# ActiveHeadphone.net
KiCad netlist of a schematic drawn in EAGLE
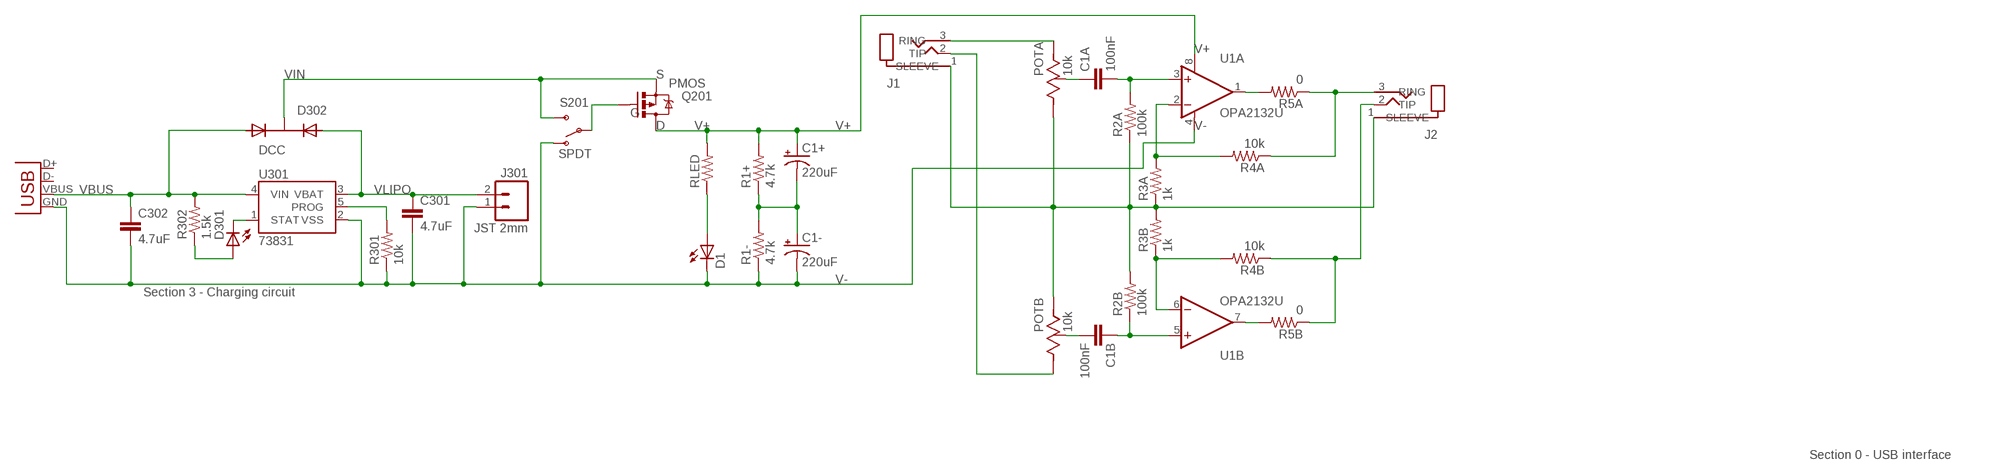
[diagram p0: schematic, sheet 1]

(export (version "E")
  (design (tool "Eeschema 10.0.6"))
  (components
    (comp (ref "C1+")
      (value "220uF")
      (footprint "eagle-import:EIA7343")
      (libsource (lib "eagle-import") (part "CAP_POL7343"))
    )
    (comp (ref "C1-")
      (value "220uF")
      (footprint "eagle-import:EIA7343")
      (libsource (lib "eagle-import") (part "CAP_POL7343"))
    )
    (comp (ref "C1A")
      (value "100nF")
      (footprint "eagle-import:0603-CAP")
      (libsource (lib "eagle-import") (part "CAP0603-CAP"))
    )
    (comp (ref "C1B")
      (value "100nF")
      (footprint "eagle-import:0603-CAP")
      (libsource (lib "eagle-import") (part "CAP0603-CAP"))
    )
    (comp (ref "C301")
      (value "4.7uF")
      (footprint "eagle-import:0603-CAP")
      (libsource (lib "eagle-import") (part "CAP0603-CAP"))
    )
    (comp (ref "C302")
      (value "4.7uF")
      (footprint "eagle-import:0603-CAP")
      (libsource (lib "eagle-import") (part "CAP0603-CAP"))
    )
    (comp (ref "D1")
      (value "RED")
      (footprint "eagle-import:LED-0603")
      (libsource (lib "eagle-import") (part "LED0603"))
    )
    (comp (ref "D301")
      (value "RED")
      (footprint "eagle-import:LED-0603")
      (libsource (lib "eagle-import") (part "LED0603"))
    )
    (comp (ref "D302")
      (value "DCC")
      (footprint "eagle-import:SOT-23-3")
      (libsource (lib "eagle-import") (part "PMEG2005CT"))
    )
    (comp (ref "J1")
      (value "3.5mm")
      (footprint "eagle-import:SJ1-3513-SMT")
      (libsource (lib "eagle-import") (part "SJ1-3513-SMT"))
    )
    (comp (ref "J2")
      (value "3.5mm")
      (footprint "eagle-import:SJ1-3513-SMT")
      (libsource (lib "eagle-import") (part "SJ1-3513-SMT"))
    )
    (comp (ref "J003")
      (value "USBSMD")
      (footprint "eagle-import:USB-MINIB")
      (libsource (lib "eagle-import") (part "USBSMD"))
    )
    (comp (ref "J301")
      (value "JST 2mm")
      (footprint "eagle-import:JST-2-SMD")
      (libsource (lib "eagle-import") (part "M02-JST-2MM-SMT"))
    )
    (comp (ref "POTA")
      (value "10k")
      (footprint "eagle-import:3352T")
      (libsource (lib "eagle-import") (part "3352T"))
    )
    (comp (ref "POTB")
      (value "10k")
      (footprint "eagle-import:3352T")
      (libsource (lib "eagle-import") (part "3352T"))
    )
    (comp (ref "Q201")
      (value "PMOS")
      (footprint "eagle-import:SOT23-3")
      (libsource (lib "eagle-import") (part "MOSFET-PCHANNELSMD"))
    )
    (comp (ref "R1+")
      (value "4.7k")
      (footprint "eagle-import:0603-RES")
      (libsource (lib "eagle-import") (part "RESISTOR0603-RES"))
    )
    (comp (ref "R1-")
      (value "4.7k")
      (footprint "eagle-import:0603-RES")
      (libsource (lib "eagle-import") (part "RESISTOR0603-RES"))
    )
    (comp (ref "R2A")
      (value "100k")
      (footprint "eagle-import:0603-RES")
      (libsource (lib "eagle-import") (part "RESISTOR0603-RES"))
    )
    (comp (ref "R2B")
      (value "100k")
      (footprint "eagle-import:0603-RES")
      (libsource (lib "eagle-import") (part "RESISTOR0603-RES"))
    )
    (comp (ref "R3A")
      (value "1k")
      (footprint "eagle-import:0603-RES")
      (libsource (lib "eagle-import") (part "RESISTOR0603-RES"))
    )
    (comp (ref "R3B")
      (value "1k")
      (footprint "eagle-import:0603-RES")
      (libsource (lib "eagle-import") (part "RESISTOR0603-RES"))
    )
    (comp (ref "R4A")
      (value "10k")
      (footprint "eagle-import:0603-RES")
      (libsource (lib "eagle-import") (part "RESISTOR0603-RES"))
    )
    (comp (ref "R4B")
      (value "10k")
      (footprint "eagle-import:0603-RES")
      (libsource (lib "eagle-import") (part "RESISTOR0603-RES"))
    )
    (comp (ref "R5A")
      (value "0")
      (footprint "eagle-import:0603-RES")
      (libsource (lib "eagle-import") (part "RESISTOR0603-RES"))
    )
    (comp (ref "R5B")
      (value "0")
      (footprint "eagle-import:0603-RES")
      (libsource (lib "eagle-import") (part "RESISTOR0603-RES"))
    )
    (comp (ref "R301")
      (value "10k")
      (footprint "eagle-import:0603-RES")
      (libsource (lib "eagle-import") (part "RESISTOR0603-RES"))
    )
    (comp (ref "R302")
      (value "1.5k")
      (footprint "eagle-import:0603-RES")
      (libsource (lib "eagle-import") (part "RESISTOR0603-RES"))
    )
    (comp (ref "RLED")
      (value "RESISTOR0603-RES")
      (footprint "eagle-import:0603-RES")
      (libsource (lib "eagle-import") (part "RESISTOR0603-RES"))
    )
    (comp (ref "S201")
      (value "SPDT")
      (footprint "eagle-import:AYZ0202")
      (libsource (lib "eagle-import") (part "SWITCH-SPSTSMD"))
    )
    (comp (ref "U1")
      (value "OPA2132U")
      (footprint "eagle-import:SO08")
      (fields (field (name "MF") "TEXAS INSTRUMENTS"))
      (libsource (lib "eagle-import") (part "OPA2132U"))
    )
    (comp (ref "U301")
      (value "73831")
      (footprint "eagle-import:SOT23-5")
      (libsource (lib "eagle-import") (part "MCP73831"))
    )
  )
  (nets
    (net (code "1") (name "/V+") (class "Default")
      (node (ref "C1+") (pin "A") (pinfunction "+_A") (pintype "passive"))
      (node (ref "Q201") (pin "3") (pinfunction "D_3") (pintype "passive"))
      (node (ref "R1+") (pin "2") (pinfunction "2_2") (pintype "passive"))
      (node (ref "RLED") (pin "2") (pinfunction "2_2") (pintype "passive"))
      (node (ref "U1") (pin "8") (pinfunction "V+_8") (pintype "power_in"))
    )
    (net (code "2") (name "/V-") (class "Default")
      (node (ref "C1-") (pin "C") (pinfunction "-_C") (pintype "passive"))
      (node (ref "C301") (pin "2") (pinfunction "2_2") (pintype "passive"))
      (node (ref "C302") (pin "2") (pinfunction "2_2") (pintype "passive"))
      (node (ref "D1") (pin "C") (pinfunction "C_C") (pintype "passive"))
      (node (ref "J003") (pin "GND") (pinfunction "GND_GND") (pintype "bidirectional"))
      (node (ref "J301") (pin "1") (pinfunction "1_1") (pintype "passive"))
      (node (ref "R1-") (pin "1") (pinfunction "1_1") (pintype "passive"))
      (node (ref "R301") (pin "1") (pinfunction "1_1") (pintype "passive"))
      (node (ref "S201") (pin "1") (pinfunction "O_1") (pintype "passive"))
      (node (ref "U1") (pin "4") (pinfunction "V-_4") (pintype "power_in"))
      (node (ref "U301") (pin "2") (pinfunction "VSS_2") (pintype "power_in"))
    )
    (net (code "3") (name "/VBUS") (class "Default")
      (node (ref "C302") (pin "1") (pinfunction "1_1") (pintype "passive"))
      (node (ref "D302") (pin "1") (pinfunction "A1_1") (pintype "passive"))
      (node (ref "J003") (pin "VBUS") (pinfunction "VBUS_VBUS") (pintype "bidirectional"))
      (node (ref "R302") (pin "2") (pinfunction "2_2") (pintype "passive"))
      (node (ref "U301") (pin "4") (pinfunction "VIN_4") (pintype "power_in"))
    )
    (net (code "4") (name "/VIN") (class "Default")
      (node (ref "D302") (pin "3") (pinfunction "K_3") (pintype "passive"))
      (node (ref "Q201") (pin "2") (pinfunction "S_2") (pintype "passive"))
      (node (ref "S201") (pin "3") (pinfunction "S_3") (pintype "passive"))
    )
    (net (code "5") (name "/VLIPO") (class "Default")
      (node (ref "C301") (pin "1") (pinfunction "1_1") (pintype "passive"))
      (node (ref "D302") (pin "2") (pinfunction "A2_2") (pintype "passive"))
      (node (ref "J301") (pin "2") (pinfunction "2_2") (pintype "passive"))
      (node (ref "U301") (pin "3") (pinfunction "VBAT_3") (pintype "power_in"))
    )
    (net (code "6") (name "Net-(C1+--)") (class "Default")
      (node (ref "C1+") (pin "C") (pinfunction "-_C") (pintype "passive"))
      (node (ref "C1-") (pin "A") (pinfunction "+_A") (pintype "passive"))
      (node (ref "R1+") (pin "1") (pinfunction "1_1") (pintype "passive"))
      (node (ref "R1-") (pin "2") (pinfunction "2_2") (pintype "passive"))
    )
    (net (code "7") (name "Net-(D1-PadA)") (class "Default")
      (node (ref "D1") (pin "A") (pinfunction "A_A") (pintype "passive"))
      (node (ref "RLED") (pin "1") (pinfunction "1_1") (pintype "passive"))
    )
    (net (code "8") (name "Net-(D301-PadA)") (class "Default")
      (node (ref "D301") (pin "A") (pinfunction "A_A") (pintype "passive"))
      (node (ref "R302") (pin "1") (pinfunction "1_1") (pintype "passive"))
    )
    (net (code "9") (name "Net-(J1-RING)") (class "Default")
      (node (ref "J1") (pin "3") (pinfunction "RING_3") (pintype "bidirectional"))
      (node (ref "POTA") (pin "3") (pinfunction "CW_3") (pintype "bidirectional"))
    )
    (net (code "10") (name "Net-(J1-SLEEVE)") (class "Default")
      (node (ref "J1") (pin "1") (pinfunction "SLEEVE_1") (pintype "bidirectional"))
      (node (ref "J2") (pin "1") (pinfunction "SLEEVE_1") (pintype "bidirectional"))
      (node (ref "POTA") (pin "1") (pinfunction "CCW_1") (pintype "bidirectional"))
      (node (ref "POTB") (pin "3") (pinfunction "CW_3") (pintype "bidirectional"))
      (node (ref "R2A") (pin "1") (pinfunction "1_1") (pintype "passive"))
      (node (ref "R2B") (pin "2") (pinfunction "2_2") (pintype "passive"))
      (node (ref "R3A") (pin "1") (pinfunction "1_1") (pintype "passive"))
      (node (ref "R3B") (pin "2") (pinfunction "2_2") (pintype "passive"))
    )
    (net (code "11") (name "Net-(J1-TIP)") (class "Default")
      (node (ref "J1") (pin "2") (pinfunction "TIP_2") (pintype "bidirectional"))
      (node (ref "POTB") (pin "1") (pinfunction "CCW_1") (pintype "bidirectional"))
    )
    (net (code "12") (name "Net-(J2-RING)") (class "Default")
      (node (ref "J2") (pin "3") (pinfunction "RING_3") (pintype "bidirectional"))
      (node (ref "R4A") (pin "1") (pinfunction "1_1") (pintype "passive"))
      (node (ref "R5A") (pin "1") (pinfunction "1_1") (pintype "passive"))
    )
    (net (code "13") (name "Net-(J2-TIP)") (class "Default")
      (node (ref "J2") (pin "2") (pinfunction "TIP_2") (pintype "bidirectional"))
      (node (ref "R4B") (pin "1") (pinfunction "1_1") (pintype "passive"))
      (node (ref "R5B") (pin "1") (pinfunction "1_1") (pintype "passive"))
    )
    (net (code "14") (name "Net-(POTA-WIPER)") (class "Default")
      (node (ref "C1A") (pin "1") (pinfunction "1_1") (pintype "passive"))
      (node (ref "POTA") (pin "2") (pinfunction "WIPER_2") (pintype "bidirectional"))
    )
    (net (code "15") (name "Net-(POTB-WIPER)") (class "Default")
      (node (ref "C1B") (pin "2") (pinfunction "2_2") (pintype "passive"))
      (node (ref "POTB") (pin "2") (pinfunction "WIPER_2") (pintype "bidirectional"))
    )
    (net (code "16") (name "Net-(Q201-G)") (class "Default")
      (node (ref "Q201") (pin "1") (pinfunction "G_1") (pintype "passive"))
      (node (ref "S201") (pin "2") (pinfunction "P_2") (pintype "passive"))
    )
    (net (code "17") (name "Net-(U1A-+IN)") (class "Default")
      (node (ref "C1A") (pin "2") (pinfunction "2_2") (pintype "passive"))
      (node (ref "R2A") (pin "2") (pinfunction "2_2") (pintype "passive"))
      (node (ref "U1") (pin "3") (pinfunction "+IN_3") (pintype "input"))
    )
    (net (code "18") (name "Net-(U1A--IN)") (class "Default")
      (node (ref "R3A") (pin "2") (pinfunction "2_2") (pintype "passive"))
      (node (ref "R4A") (pin "2") (pinfunction "2_2") (pintype "passive"))
      (node (ref "U1") (pin "2") (pinfunction "-IN_2") (pintype "input"))
    )
    (net (code "19") (name "Net-(U1A-OUT)") (class "Default")
      (node (ref "R5A") (pin "2") (pinfunction "2_2") (pintype "passive"))
      (node (ref "U1") (pin "1") (pinfunction "OUT_1") (pintype "output"))
    )
    (net (code "20") (name "Net-(U1B-+IN)") (class "Default")
      (node (ref "C1B") (pin "1") (pinfunction "1_1") (pintype "passive"))
      (node (ref "R2B") (pin "1") (pinfunction "1_1") (pintype "passive"))
      (node (ref "U1") (pin "5") (pinfunction "+IN_5") (pintype "input"))
    )
    (net (code "21") (name "Net-(U1B--IN)") (class "Default")
      (node (ref "R3B") (pin "1") (pinfunction "1_1") (pintype "passive"))
      (node (ref "R4B") (pin "2") (pinfunction "2_2") (pintype "passive"))
      (node (ref "U1") (pin "6") (pinfunction "-IN_6") (pintype "input"))
    )
    (net (code "22") (name "Net-(U1B-OUT)") (class "Default")
      (node (ref "R5B") (pin "2") (pinfunction "2_2") (pintype "passive"))
      (node (ref "U1") (pin "7") (pinfunction "OUT_7") (pintype "output"))
    )
    (net (code "23") (name "Net-(U301-PROG)") (class "Default")
      (node (ref "R301") (pin "2") (pinfunction "2_2") (pintype "passive"))
      (node (ref "U301") (pin "5") (pinfunction "PROG_5") (pintype "input"))
    )
    (net (code "24") (name "Net-(U301-STAT)") (class "Default")
      (node (ref "D301") (pin "C") (pinfunction "C_C") (pintype "passive"))
      (node (ref "U301") (pin "1") (pinfunction "STAT_1") (pintype "output"))
    )
    (net (code "25") (name "unconnected-(J003-PadD+)") (class "Default")
      (node (ref "J003") (pin "D+") (pinfunction "D+_D+") (pintype "bidirectional"))
    )
    (net (code "26") (name "unconnected-(J003-PadD-)") (class "Default")
      (node (ref "J003") (pin "D-") (pinfunction "D-_D-") (pintype "bidirectional"))
    )
  )
)
